# v1.net
KiCad netlist of a schematic drawn in EAGLE
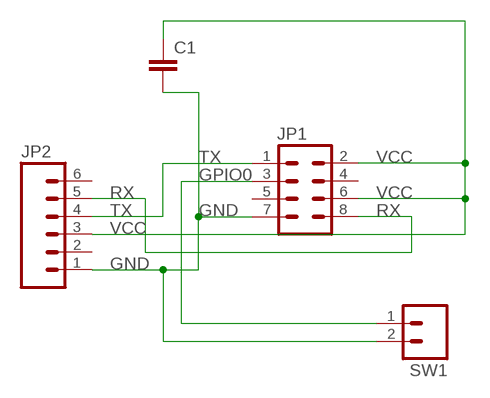
[diagram p0: schematic, sheet 1]

(export (version "E")
  (design (tool "Eeschema 10.0.6"))
  (components
    (comp (ref "C1")
      (value "CAPPTH")
      (footprint "eagle-import:CAP-PTH-SMALL")
      (libsource (lib "eagle-import") (part "CAPPTH"))
    )
    (comp (ref "JP1")
      (value "M04X2")
      (footprint "eagle-import:2X4")
      (libsource (lib "eagle-import") (part "M04X2"))
    )
    (comp (ref "JP2")
      (value "M06SILK_FEMALE_PTH")
      (footprint "eagle-import:1X06")
      (libsource (lib "eagle-import") (part "M06SILK_FEMALE_PTH"))
    )
    (comp (ref "SW1")
      (value "M02PTH")
      (footprint "eagle-import:1X02")
      (libsource (lib "eagle-import") (part "M02PTH"))
    )
  )
  (nets
    (net (code "1") (name "/GND") (class "Default")
      (node (ref "C1") (pin "2") (pinfunction "2_2") (pintype "passive"))
      (node (ref "JP1") (pin "7") (pinfunction "7_7") (pintype "passive"))
      (node (ref "JP2") (pin "1") (pinfunction "1_1") (pintype "passive"))
      (node (ref "SW1") (pin "2") (pinfunction "2_2") (pintype "passive"))
    )
    (net (code "2") (name "/GPIO0") (class "Default")
      (node (ref "JP1") (pin "3") (pinfunction "3_3") (pintype "passive"))
      (node (ref "SW1") (pin "1") (pinfunction "1_1") (pintype "passive"))
    )
    (net (code "3") (name "/RX") (class "Default")
      (node (ref "JP1") (pin "8") (pinfunction "8_8") (pintype "passive"))
      (node (ref "JP2") (pin "5") (pinfunction "5_5") (pintype "passive"))
    )
    (net (code "4") (name "/TX") (class "Default")
      (node (ref "JP1") (pin "1") (pinfunction "1_1") (pintype "passive"))
      (node (ref "JP2") (pin "4") (pinfunction "4_4") (pintype "passive"))
    )
    (net (code "5") (name "/VCC") (class "Default")
      (node (ref "C1") (pin "1") (pinfunction "1_1") (pintype "passive"))
      (node (ref "JP1") (pin "2") (pinfunction "2_2") (pintype "passive"))
      (node (ref "JP1") (pin "6") (pinfunction "6_6") (pintype "passive"))
      (node (ref "JP2") (pin "3") (pinfunction "3_3") (pintype "passive"))
    )
    (net (code "6") (name "unconnected-(JP1-Pad4)") (class "Default")
      (node (ref "JP1") (pin "4") (pinfunction "4_4") (pintype "passive"))
    )
    (net (code "7") (name "unconnected-(JP1-Pad5)") (class "Default")
      (node (ref "JP1") (pin "5") (pinfunction "5_5") (pintype "passive"))
    )
    (net (code "8") (name "unconnected-(JP2-Pad2)") (class "Default")
      (node (ref "JP2") (pin "2") (pinfunction "2_2") (pintype "passive"))
    )
    (net (code "9") (name "unconnected-(JP2-Pad6)") (class "Default")
      (node (ref "JP2") (pin "6") (pinfunction "6_6") (pintype "passive"))
    )
  )
)
